# Peripheral.net
KiCad netlist of a schematic drawn in Altium Designer
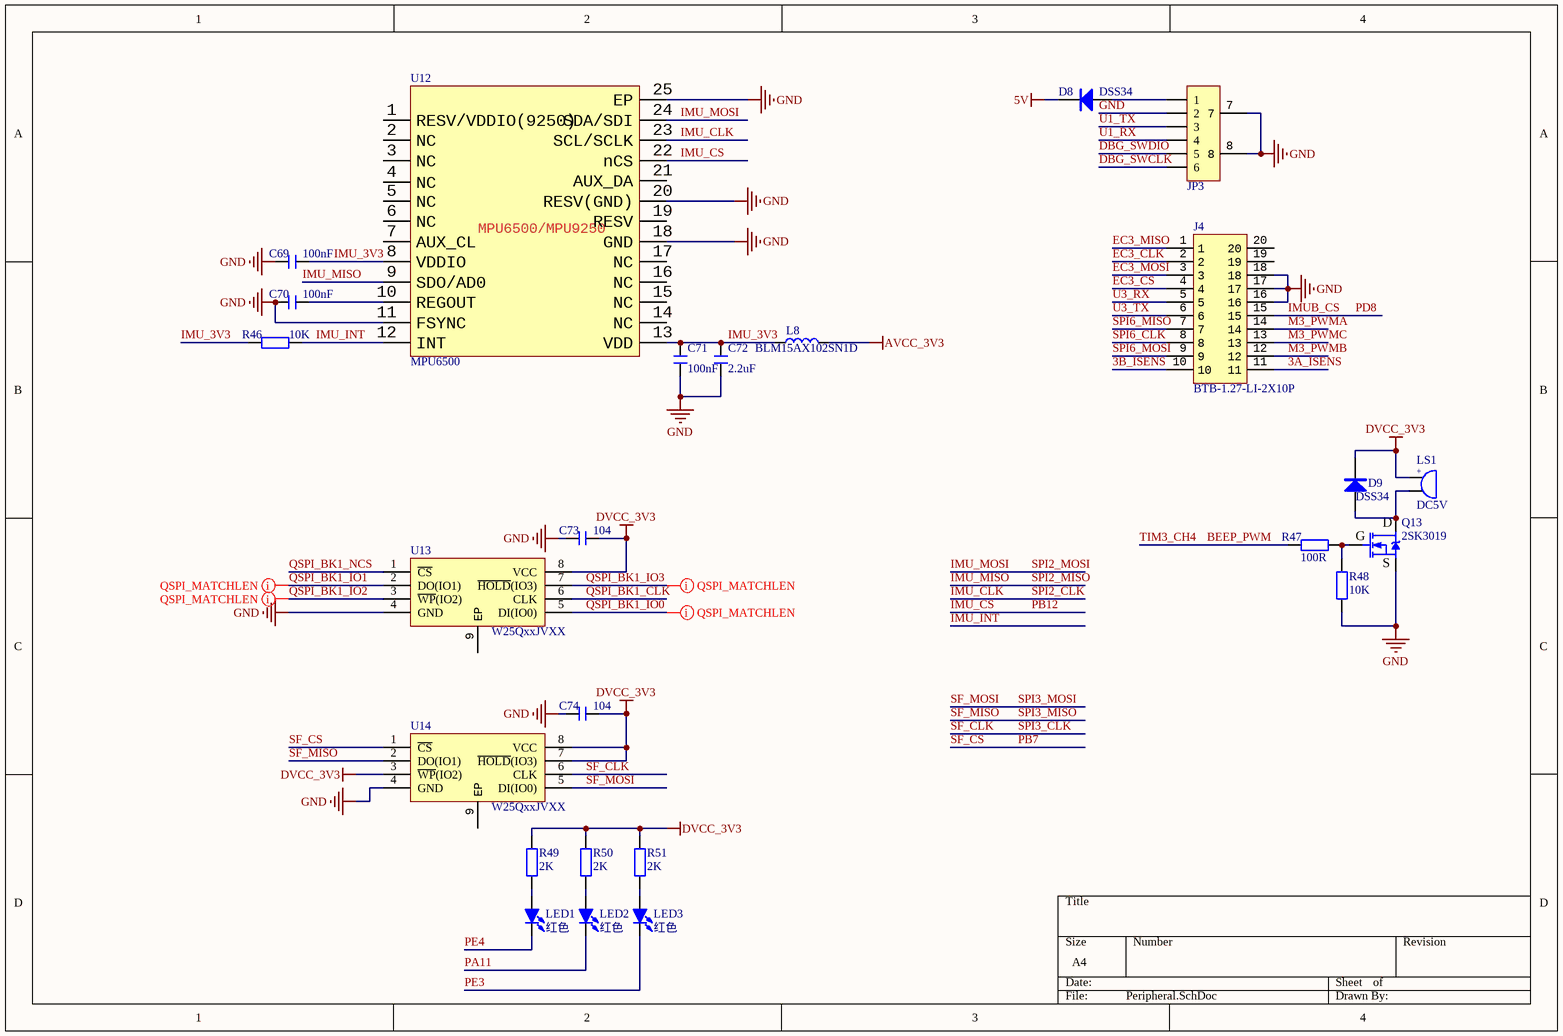
[diagram p0: Peripheral.SchDoc]

(export (version "E")
  (design (tool "Eeschema 10.0.6"))
  (components
    (comp (ref "C69")
      (value "100nF")
      (footprint "C 0402_L")
      (description "无极性贴片电容")
      (fields (field (name "版权归属") "源创客"))
      (libsource (lib "3.1   - 电阻-电容-电感") (part "C"))
    )
    (comp (ref "C70")
      (value "100nF")
      (footprint "C 0402_L")
      (description "无极性贴片电容")
      (fields (field (name "版权归属") "源创客"))
      (libsource (lib "3.1   - 电阻-电容-电感") (part "C"))
    )
    (comp (ref "C71")
      (value "100nF")
      (footprint "C 0402_L")
      (description "无极性贴片电容")
      (fields (field (name "版权归属") "源创客"))
      (libsource (lib "3.1   - 电阻-电容-电感") (part "C"))
    )
    (comp (ref "C72")
      (value "2.2uF")
      (footprint "C 0402_L")
      (description "无极性贴片电容")
      (fields (field (name "版权归属") "源创客"))
      (libsource (lib "3.1   - 电阻-电容-电感") (part "C"))
    )
    (comp (ref "C73")
      (value "104")
      (footprint "C 0402_L")
      (description "无极性贴片电容")
      (fields (field (name "版权归属") "源创客"))
      (libsource (lib "3.1   - 电阻-电容-电感") (part "C"))
    )
    (comp (ref "C74")
      (value "104")
      (footprint "C 0402_L")
      (description "无极性贴片电容")
      (fields (field (name "版权归属") "源创客"))
      (libsource (lib "3.1   - 电阻-电容-电感") (part "C"))
    )
    (comp (ref "D8")
      (value "DSS34")
      (footprint "SOD-123FL")
      (description "肖特基二极管")
      (libsource (lib "8.1   - 二极管-整流桥") (part "DSS34"))
    )
    (comp (ref "D9")
      (value "DSS34")
      (footprint "SOD-123FL")
      (description "肖特基二极管")
      (libsource (lib "8.1   - 二极管-整流桥") (part "DSS34"))
    )
    (comp (ref "J4")
      (value "BTB-1.27-LI-2X10P")
      (footprint "1.27-LI-2X10P")
      (libsource (lib "4.16 - BTB连接器 - 1.27") (part "LI-2X10P"))
    )
    (comp (ref "JP3")
      (value "HDR-1X6")
      (footprint "GH1.25-WS-6P")
      (description "6P接插件")
      (fields (field (name "版权归属") "源创客"))
      (libsource (lib "4.2   - 接插件-脚距1.25") (part "Header 6"))
    )
    (comp (ref "L8")
      (value "BLM15AX102SN1D")
      (footprint "L 0402")
      (description "小功率贴片电感")
      (fields (field (name "版权归属") "源创客"))
      (libsource (lib "3.1   - 电阻-电容-电感") (part "L"))
    )
    (comp (ref "LED1")
      (value "红色")
      (footprint "LED 0402R")
      (description "贴片LED")
      (fields (field (name "版权归属") "源创客"))
      (libsource (lib "9.1   - LED") (part "LED-SMD"))
    )
    (comp (ref "LED2")
      (value "红色")
      (footprint "LED 0402R")
      (description "贴片LED")
      (fields (field (name "版权归属") "源创客"))
      (libsource (lib "9.1   - LED") (part "LED-SMD"))
    )
    (comp (ref "LED3")
      (value "红色")
      (footprint "LED 0402R")
      (description "贴片LED")
      (fields (field (name "版权归属") "源创客"))
      (libsource (lib "9.1   - LED") (part "LED-SMD"))
    )
    (comp (ref "LS1")
      (value "DC5V")
      (footprint "BEEP_SMD_SBZ9032C03R16")
      (description "蜂鸣器")
      (fields (field (name "版权归属") "源创客"))
      (libsource (lib "15.1 - 未分类器件") (part "BEEP"))
    )
    (comp (ref "Q13")
      (value "2SK3019")
      (footprint "SOT523")
      (description "N沟道场效应管")
      (libsource (lib "6.1   - 场效应管-可控硅") (part "2SK3019"))
    )
    (comp (ref "R46")
      (value "10K")
      (footprint "R 0402_L")
      (description "贴片电阻")
      (fields (field (name "版权归属") "源创客"))
      (libsource (lib "3.1   - 电阻-电容-电感") (part "R"))
    )
    (comp (ref "R47")
      (value "100R")
      (footprint "R 0402_L")
      (description "贴片电阻")
      (fields (field (name "版权归属") "源创客"))
      (libsource (lib "3.1   - 电阻-电容-电感") (part "R"))
    )
    (comp (ref "R48")
      (value "10K")
      (footprint "R 0402_L")
      (description "贴片电阻")
      (fields (field (name "版权归属") "源创客"))
      (libsource (lib "3.1   - 电阻-电容-电感") (part "R"))
    )
    (comp (ref "R49")
      (value "2K")
      (footprint "R 0402_L")
      (description "贴片电阻")
      (fields (field (name "版权归属") "源创客"))
      (libsource (lib "3.1   - 电阻-电容-电感") (part "R"))
    )
    (comp (ref "R50")
      (value "2K")
      (footprint "R 0402_L")
      (description "贴片电阻")
      (fields (field (name "版权归属") "源创客"))
      (libsource (lib "3.1   - 电阻-电容-电感") (part "R"))
    )
    (comp (ref "R51")
      (value "2K")
      (footprint "R 0402_L")
      (description "贴片电阻")
      (fields (field (name "版权归属") "源创客"))
      (libsource (lib "3.1   - 电阻-电容-电感") (part "R"))
    )
    (comp (ref "U12")
      (value "MPU6500")
      (footprint "QFN24 3X3")
      (description "6轴IMU")
      (libsource (lib "11.1 - 传感元件") (part "MPU6500"))
    )
    (comp (ref "U13")
      (value "W25QxxJVXX")
      (footprint "SOP8W_L")
      (description "外置Flash")
      (fields (field (name "版权归属") "源创客"))
      (libsource (lib "1.1   - IC芯片") (part "W25Qxx"))
    )
    (comp (ref "U14")
      (value "W25QxxJVXX")
      (footprint "SOP8W_L")
      (description "外置Flash")
      (fields (field (name "版权归属") "源创客"))
      (libsource (lib "1.1   - IC芯片") (part "W25Qxx"))
    )
  )
  (nets
    (net (code "1") (name "/3A_ISENS") (class "Default")
      (node (ref "J4") (pin "11") (pinfunction "11_11") (pintype "passive"))
    )
    (net (code "2") (name "/3B_ISENS") (class "Default")
      (node (ref "J4") (pin "10") (pinfunction "10_10") (pintype "passive"))
    )
    (net (code "3") (name "/BEEP_PWM") (class "Default")
      (node (ref "R47") (pin "1") (pinfunction "1_1") (pintype "passive"))
    )
    (net (code "4") (name "/DBG_SWCLK") (class "Default")
      (node (ref "JP3") (pin "6") (pinfunction "6_6") (pintype "passive"))
    )
    (net (code "5") (name "/DBG_SWDIO") (class "Default")
      (node (ref "JP3") (pin "5") (pinfunction "5_5") (pintype "passive"))
    )
    (net (code "6") (name "/EC3_CLK") (class "Default")
      (node (ref "J4") (pin "2") (pinfunction "2_2") (pintype "passive"))
    )
    (net (code "7") (name "/EC3_CS") (class "Default")
      (node (ref "J4") (pin "4") (pinfunction "4_4") (pintype "passive"))
    )
    (net (code "8") (name "/EC3_MISO") (class "Default")
      (node (ref "J4") (pin "1") (pinfunction "1_1") (pintype "passive"))
    )
    (net (code "9") (name "/EC3_MOSI") (class "Default")
      (node (ref "J4") (pin "3") (pinfunction "3_3") (pintype "passive"))
    )
    (net (code "10") (name "/IMUB_CS") (class "Default")
      (node (ref "J4") (pin "15") (pinfunction "15_15") (pintype "passive"))
    )
    (net (code "11") (name "/IMU_3V3") (class "Default")
      (node (ref "C69") (pin "1") (pinfunction "1_1") (pintype "passive"))
      (node (ref "C71") (pin "2") (pinfunction "2_2") (pintype "passive"))
      (node (ref "C72") (pin "2") (pinfunction "2_2") (pintype "passive"))
      (node (ref "L8") (pin "1") (pinfunction "1_1") (pintype "passive"))
      (node (ref "R46") (pin "1") (pinfunction "1_1") (pintype "passive"))
      (node (ref "U12") (pin "13") (pinfunction "VDD_13") (pintype "passive"))
      (node (ref "U12") (pin "8") (pinfunction "VDDIO_8") (pintype "passive"))
    )
    (net (code "12") (name "/IMU_CLK") (class "Default")
      (node (ref "U12") (pin "23") (pinfunction "SCL/SCLK_23") (pintype "passive"))
    )
    (net (code "13") (name "/IMU_CS") (class "Default")
      (node (ref "U12") (pin "22") (pinfunction "nCS_22") (pintype "passive"))
    )
    (net (code "14") (name "/IMU_INT") (class "Default")
      (node (ref "R46") (pin "2") (pinfunction "2_2") (pintype "passive"))
      (node (ref "U12") (pin "12") (pinfunction "INT_12") (pintype "passive"))
    )
    (net (code "15") (name "/IMU_MISO") (class "Default")
      (node (ref "U12") (pin "9") (pinfunction "SDO/AD0_9") (pintype "passive"))
    )
    (net (code "16") (name "/IMU_MOSI") (class "Default")
      (node (ref "U12") (pin "24") (pinfunction "SDA/SDI_24") (pintype "passive"))
    )
    (net (code "17") (name "/M3_PWMA") (class "Default")
      (node (ref "J4") (pin "14") (pinfunction "14_14") (pintype "passive"))
    )
    (net (code "18") (name "/M3_PWMB") (class "Default")
      (node (ref "J4") (pin "12") (pinfunction "12_12") (pintype "passive"))
    )
    (net (code "19") (name "/M3_PWMC") (class "Default")
      (node (ref "J4") (pin "13") (pinfunction "13_13") (pintype "passive"))
    )
    (net (code "20") (name "/PA11") (class "Default")
      (node (ref "LED2") (pin "1") (pinfunction "K_1") (pintype "passive"))
    )
    (net (code "21") (name "/PB7") (class "Default")
      (node (ref "U14") (pin "1") (pinfunction "~{CS}_1") (pintype "passive"))
    )
    (net (code "22") (name "/PE3") (class "Default")
      (node (ref "LED3") (pin "1") (pinfunction "K_1") (pintype "passive"))
    )
    (net (code "23") (name "/PE4") (class "Default")
      (node (ref "LED1") (pin "1") (pinfunction "K_1") (pintype "passive"))
    )
    (net (code "24") (name "/QSPI_BK1_CLK") (class "Default")
      (node (ref "U13") (pin "6") (pinfunction "CLK_6") (pintype "passive"))
    )
    (net (code "25") (name "/QSPI_BK1_IO0") (class "Default")
      (node (ref "U13") (pin "5") (pinfunction "DI(IO0)_5") (pintype "passive"))
    )
    (net (code "26") (name "/QSPI_BK1_IO1") (class "Default")
      (node (ref "U13") (pin "2") (pinfunction "DO(IO1)_2") (pintype "passive"))
    )
    (net (code "27") (name "/QSPI_BK1_IO2") (class "Default")
      (node (ref "U13") (pin "3") (pinfunction "~{WP}(IO2)_3") (pintype "passive"))
    )
    (net (code "28") (name "/QSPI_BK1_IO3") (class "Default")
      (node (ref "U13") (pin "7") (pinfunction "~{HOLD}(IO3)_7") (pintype "passive"))
    )
    (net (code "29") (name "/QSPI_BK1_NCS") (class "Default")
      (node (ref "U13") (pin "1") (pinfunction "~{CS}_1") (pintype "passive"))
    )
    (net (code "30") (name "/SF_CLK") (class "Default")
      (node (ref "U14") (pin "6") (pinfunction "CLK_6") (pintype "passive"))
    )
    (net (code "31") (name "/SF_MISO") (class "Default")
      (node (ref "U14") (pin "2") (pinfunction "DO(IO1)_2") (pintype "passive"))
    )
    (net (code "32") (name "/SF_MOSI") (class "Default")
      (node (ref "U14") (pin "5") (pinfunction "DI(IO0)_5") (pintype "passive"))
    )
    (net (code "33") (name "/SPI6_CLK") (class "Default")
      (node (ref "J4") (pin "8") (pinfunction "8_8") (pintype "passive"))
    )
    (net (code "34") (name "/SPI6_MISO") (class "Default")
      (node (ref "J4") (pin "7") (pinfunction "7_7") (pintype "passive"))
    )
    (net (code "35") (name "/SPI6_MOSI") (class "Default")
      (node (ref "J4") (pin "9") (pinfunction "9_9") (pintype "passive"))
    )
    (net (code "36") (name "/U1_RX") (class "Default")
      (node (ref "JP3") (pin "4") (pinfunction "4_4") (pintype "passive"))
    )
    (net (code "37") (name "/U1_TX") (class "Default")
      (node (ref "JP3") (pin "3") (pinfunction "3_3") (pintype "passive"))
    )
    (net (code "38") (name "/U3_RX") (class "Default")
      (node (ref "J4") (pin "5") (pinfunction "5_5") (pintype "passive"))
    )
    (net (code "39") (name "/U3_TX") (class "Default")
      (node (ref "J4") (pin "6") (pinfunction "6_6") (pintype "passive"))
    )
    (net (code "40") (name "5V") (class "Default")
      (node (ref "D8") (pin "1") (pinfunction "K_1") (pintype "passive"))
    )
    (net (code "41") (name "AVCC_3V3") (class "Default")
      (node (ref "L8") (pin "2") (pinfunction "2_2") (pintype "passive"))
    )
    (net (code "42") (name "DVCC_3V3") (class "Default")
      (node (ref "C73") (pin "2") (pinfunction "2_2") (pintype "passive"))
      (node (ref "C74") (pin "2") (pinfunction "2_2") (pintype "passive"))
      (node (ref "D9") (pin "1") (pinfunction "K_1") (pintype "passive"))
      (node (ref "LS1") (pin "1") (pinfunction "1_1") (pintype "passive"))
      (node (ref "R49") (pin "2") (pinfunction "2_2") (pintype "passive"))
      (node (ref "R50") (pin "2") (pinfunction "2_2") (pintype "passive"))
      (node (ref "R51") (pin "2") (pinfunction "2_2") (pintype "passive"))
      (node (ref "U13") (pin "8") (pinfunction "VCC_8") (pintype "passive"))
      (node (ref "U14") (pin "3") (pinfunction "~{WP}(IO2)_3") (pintype "passive"))
      (node (ref "U14") (pin "7") (pinfunction "~{HOLD}(IO3)_7") (pintype "passive"))
      (node (ref "U14") (pin "8") (pinfunction "VCC_8") (pintype "passive"))
    )
    (net (code "43") (name "GND") (class "Default")
      (node (ref "C69") (pin "2") (pinfunction "2_2") (pintype "passive"))
      (node (ref "C70") (pin "2") (pinfunction "2_2") (pintype "passive"))
      (node (ref "C71") (pin "1") (pinfunction "1_1") (pintype "passive"))
      (node (ref "C72") (pin "1") (pinfunction "1_1") (pintype "passive"))
      (node (ref "C73") (pin "1") (pinfunction "1_1") (pintype "passive"))
      (node (ref "C74") (pin "1") (pinfunction "1_1") (pintype "passive"))
      (node (ref "J4") (pin "16") (pinfunction "16_16") (pintype "passive"))
      (node (ref "J4") (pin "17") (pinfunction "17_17") (pintype "passive"))
      (node (ref "J4") (pin "18") (pinfunction "18_18") (pintype "passive"))
      (node (ref "JP3") (pin "2") (pinfunction "2_2") (pintype "passive"))
      (node (ref "JP3") (pin "7") (pinfunction "7_7") (pintype "passive"))
      (node (ref "JP3") (pin "8") (pinfunction "8_8") (pintype "passive"))
      (node (ref "Q13") (pin "2") (pinfunction "S_2") (pintype "passive"))
      (node (ref "R48") (pin "1") (pinfunction "1_1") (pintype "passive"))
      (node (ref "U12") (pin "11") (pinfunction "FSYNC_11") (pintype "passive"))
      (node (ref "U12") (pin "18") (pinfunction "GND_18") (pintype "passive"))
      (node (ref "U12") (pin "20") (pinfunction "RESV(GND)_20") (pintype "passive"))
      (node (ref "U12") (pin "25") (pinfunction "EP_25") (pintype "passive"))
      (node (ref "U13") (pin "4") (pinfunction "GND_4") (pintype "passive"))
      (node (ref "U14") (pin "4") (pinfunction "GND_4") (pintype "passive"))
    )
    (net (code "44") (name "Net-(D8-A)") (class "Default")
      (node (ref "D8") (pin "2") (pinfunction "A_2") (pintype "passive"))
      (node (ref "JP3") (pin "1") (pinfunction "1_1") (pintype "passive"))
    )
    (net (code "45") (name "Net-(D9-A)") (class "Default")
      (node (ref "D9") (pin "2") (pinfunction "A_2") (pintype "passive"))
      (node (ref "LS1") (pin "2") (pinfunction "2_2") (pintype "passive"))
      (node (ref "Q13") (pin "3") (pinfunction "D_3") (pintype "passive"))
    )
    (net (code "46") (name "Net-(LED1-A)") (class "Default")
      (node (ref "LED1") (pin "2") (pinfunction "A_2") (pintype "passive"))
      (node (ref "R49") (pin "1") (pinfunction "1_1") (pintype "passive"))
    )
    (net (code "47") (name "Net-(LED2-A)") (class "Default")
      (node (ref "LED2") (pin "2") (pinfunction "A_2") (pintype "passive"))
      (node (ref "R50") (pin "1") (pinfunction "1_1") (pintype "passive"))
    )
    (net (code "48") (name "Net-(LED3-A)") (class "Default")
      (node (ref "LED3") (pin "2") (pinfunction "A_2") (pintype "passive"))
      (node (ref "R51") (pin "1") (pinfunction "1_1") (pintype "passive"))
    )
    (net (code "49") (name "Net-(Q13-G)") (class "Default")
      (node (ref "Q13") (pin "1") (pinfunction "G_1") (pintype "passive"))
      (node (ref "R47") (pin "2") (pinfunction "2_2") (pintype "passive"))
      (node (ref "R48") (pin "2") (pinfunction "2_2") (pintype "passive"))
    )
    (net (code "50") (name "Net-(U12-REGOUT)") (class "Default")
      (node (ref "C70") (pin "1") (pinfunction "1_1") (pintype "passive"))
      (node (ref "U12") (pin "10") (pinfunction "REGOUT_10") (pintype "passive"))
    )
    (net (code "51") (name "unconnected-(J4-Pad19)") (class "Default")
      (node (ref "J4") (pin "19") (pinfunction "19_19") (pintype "passive"))
    )
    (net (code "52") (name "unconnected-(J4-Pad20)") (class "Default")
      (node (ref "J4") (pin "20") (pinfunction "20_20") (pintype "passive"))
    )
    (net (code "53") (name "unconnected-(U12-AUX_CL-Pad7)") (class "Default")
      (node (ref "U12") (pin "7") (pinfunction "AUX_CL_7") (pintype "passive"))
    )
    (net (code "54") (name "unconnected-(U12-AUX_DA-Pad21)") (class "Default")
      (node (ref "U12") (pin "21") (pinfunction "AUX_DA_21") (pintype "passive"))
    )
    (net (code "55") (name "unconnected-(U12-NC-Pad2)") (class "Default")
      (node (ref "U12") (pin "2") (pinfunction "NC_2") (pintype "passive"))
    )
    (net (code "56") (name "unconnected-(U12-NC-Pad3)") (class "Default")
      (node (ref "U12") (pin "3") (pinfunction "NC_3") (pintype "passive"))
    )
    (net (code "57") (name "unconnected-(U12-NC-Pad4)") (class "Default")
      (node (ref "U12") (pin "4") (pinfunction "NC_4") (pintype "passive"))
    )
    (net (code "58") (name "unconnected-(U12-NC-Pad5)") (class "Default")
      (node (ref "U12") (pin "5") (pinfunction "NC_5") (pintype "passive"))
    )
    (net (code "59") (name "unconnected-(U12-NC-Pad6)") (class "Default")
      (node (ref "U12") (pin "6") (pinfunction "NC_6") (pintype "passive"))
    )
    (net (code "60") (name "unconnected-(U12-NC-Pad14)") (class "Default")
      (node (ref "U12") (pin "14") (pinfunction "NC_14") (pintype "passive"))
    )
    (net (code "61") (name "unconnected-(U12-NC-Pad15)") (class "Default")
      (node (ref "U12") (pin "15") (pinfunction "NC_15") (pintype "passive"))
    )
    (net (code "62") (name "unconnected-(U12-NC-Pad16)") (class "Default")
      (node (ref "U12") (pin "16") (pinfunction "NC_16") (pintype "passive"))
    )
    (net (code "63") (name "unconnected-(U12-NC-Pad17)") (class "Default")
      (node (ref "U12") (pin "17") (pinfunction "NC_17") (pintype "passive"))
    )
    (net (code "64") (name "unconnected-(U12-RESV-Pad19)") (class "Default")
      (node (ref "U12") (pin "19") (pinfunction "RESV_19") (pintype "passive"))
    )
    (net (code "65") (name "unconnected-(U12-RESV{slash}VDDIO(9250)-Pad1)") (class "Default")
      (node (ref "U12") (pin "1") (pinfunction "RESV/VDDIO(9250)_1") (pintype "passive"))
    )
    (net (code "66") (name "unconnected-(U13-EP-Pad9)") (class "Default")
      (node (ref "U13") (pin "9") (pinfunction "EP_9") (pintype "passive"))
    )
    (net (code "67") (name "unconnected-(U14-EP-Pad9)") (class "Default")
      (node (ref "U14") (pin "9") (pinfunction "EP_9") (pintype "passive"))
    )
  )
)
